# SH_SW2_V1_0.net
KiCad netlist of a schematic drawn in Altium Designer
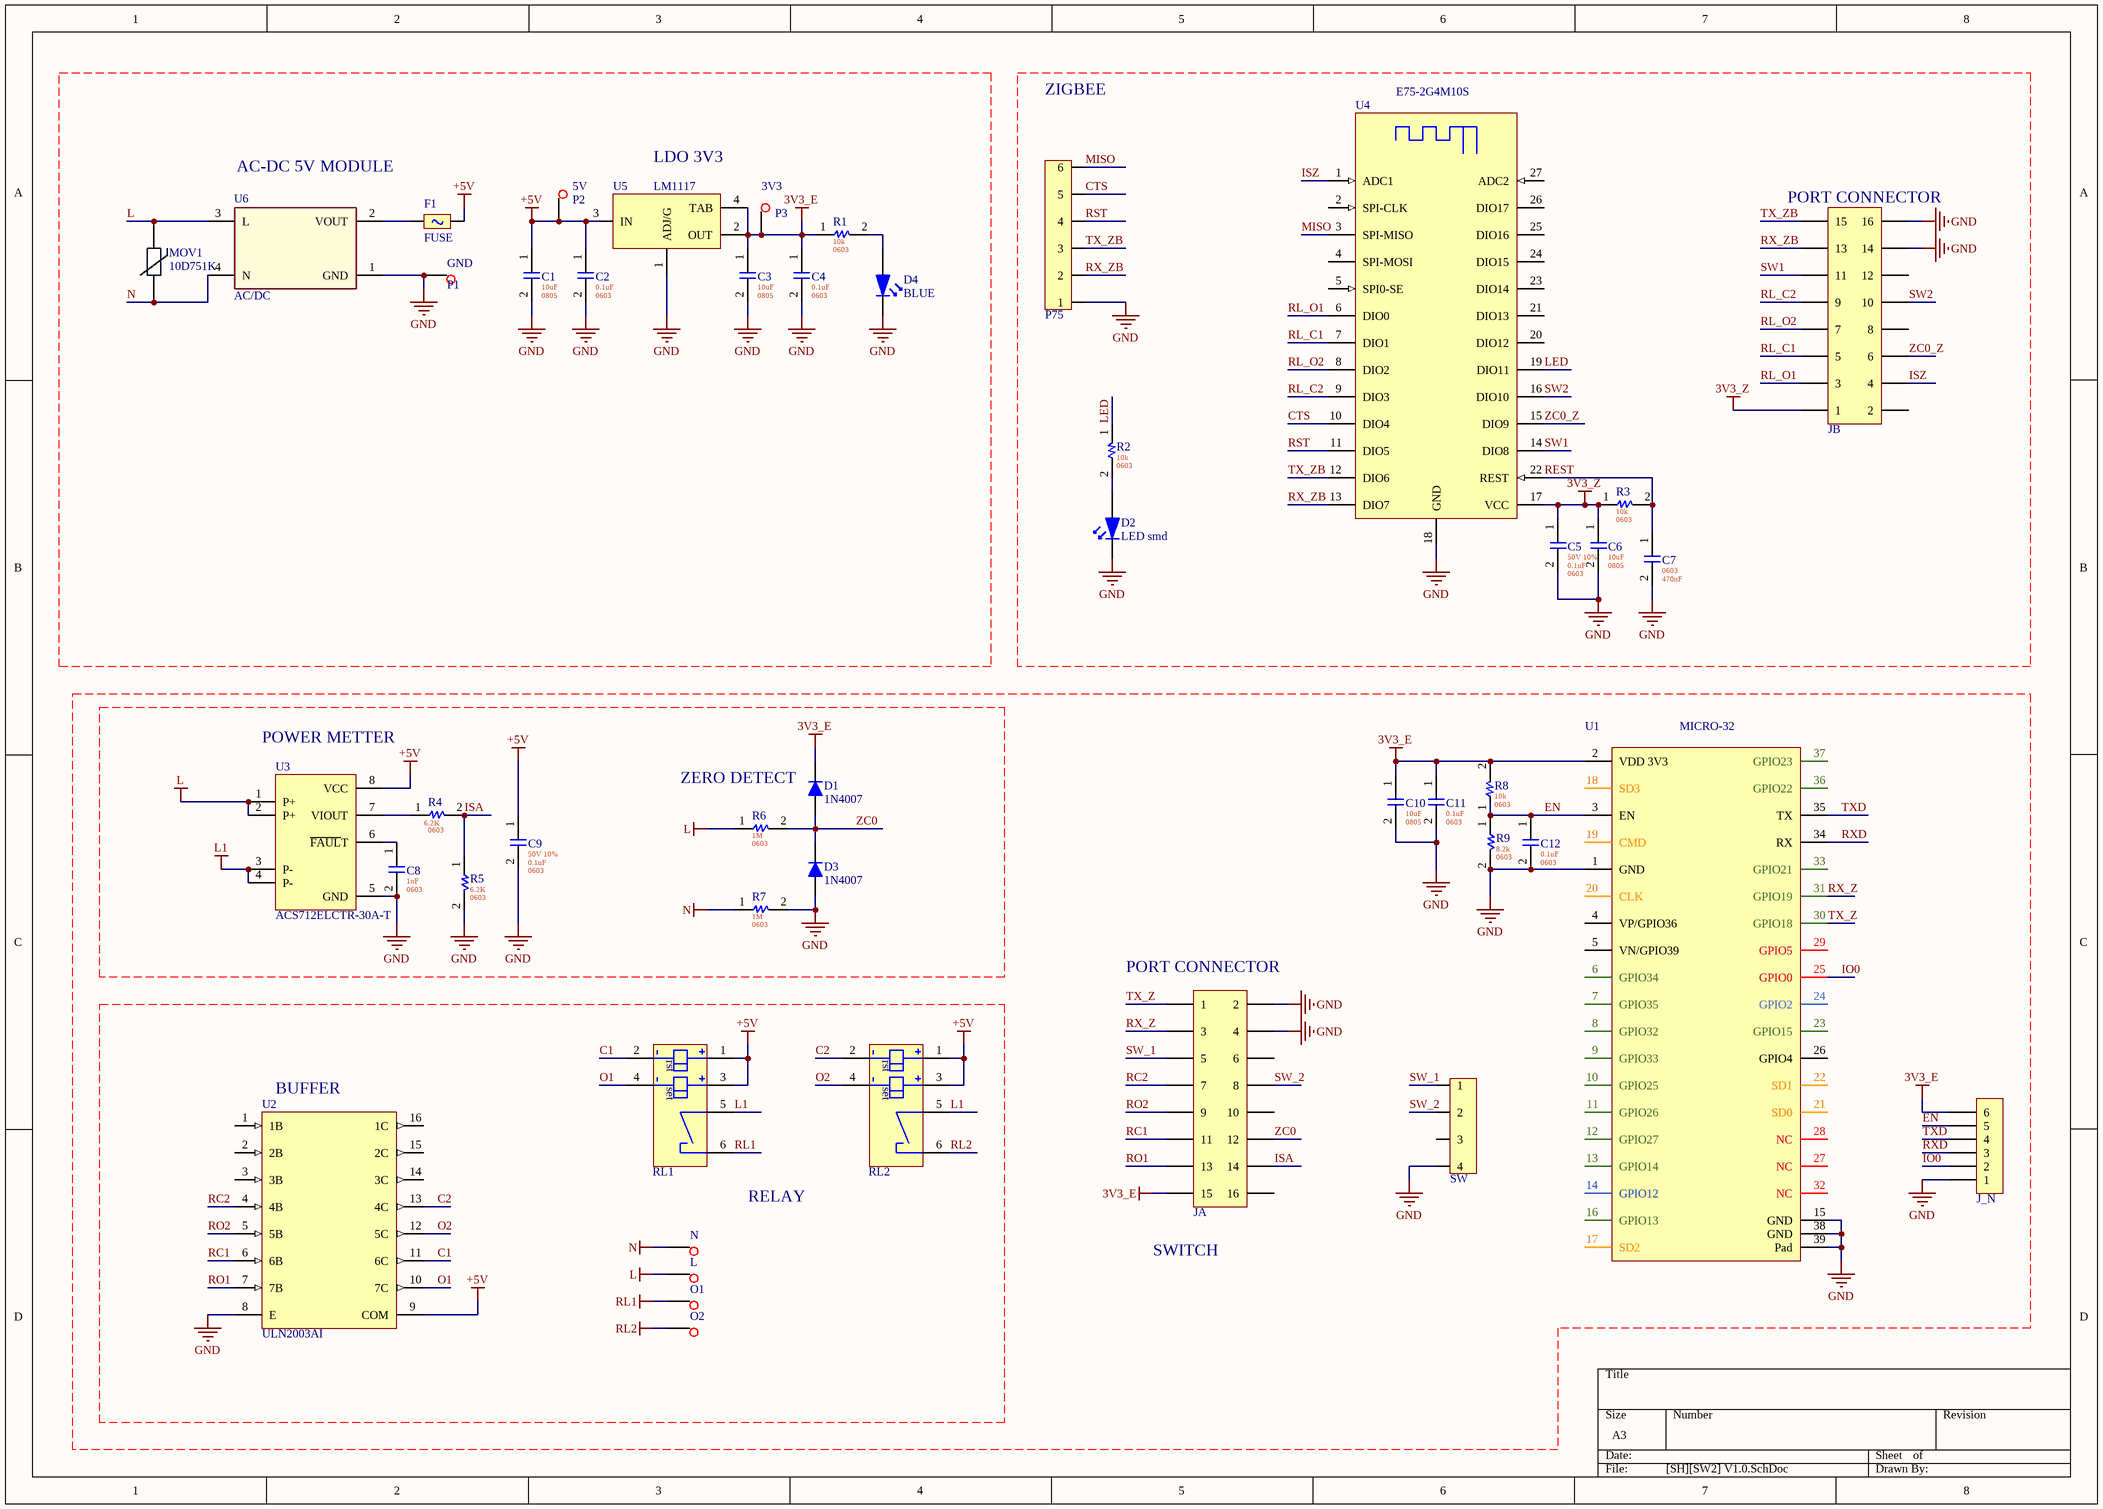
[diagram p0: [SH][SW2] V1.0.SchDoc]

(export (version "E")
  (design (tool "Eeschema 10.0.6"))
  (components
    (comp (ref "3V3") (value "P3") (footprint "TEXT_POINT") (libsource (lib "Kienlib") (part "P1")))
    (comp (ref "5V") (value "P2") (footprint "TEXT_POINT") (libsource (lib "Kienlib") (part "P1")))
    (comp (ref "C1")
      (value "10uF")
      (footprint "0805 C")
      (description "CAP CER 10uF 50V 10% 0805 SMD")
      (fields (field (name "FP") "0805") (field (name "CREATOR") "MMUOP"))
      (libsource (lib "Capacitor") (part "0805 10uF CER"))
    )
    (comp (ref "C2")
      (value "0.1uF")
      (footprint "0603 C")
      (description "CAP CER 0.1uF 50V 10% 0603 SMD")
      (fields (field (name "FP") "0603") (field (name "CREATOR") "MMUOP"))
      (libsource (lib "Capacitor") (part "0603 0.1uF CER"))
    )
    (comp (ref "C3")
      (value "10uF")
      (footprint "0805 C")
      (description "CAP CER 10uF 50V 10% 0805 SMD")
      (fields (field (name "FP") "0805") (field (name "CREATOR") "MMUOP"))
      (libsource (lib "Capacitor") (part "0805 10uF CER"))
    )
    (comp (ref "C4")
      (value "0.1uF")
      (footprint "0603 C")
      (description "CAP CER 0.1uF 50V 10% 0603 SMD")
      (fields (field (name "FP") "0603") (field (name "CREATOR") "MMUOP"))
      (libsource (lib "Capacitor") (part "0603 0.1uF CER"))
    )
    (comp (ref "C5")
      (value "0.1uF")
      (footprint "0603 C")
      (description "CAP CER 0.1uF 50V 10% 0603 SMD")
      (fields
        (field (name "VOLTAGE + TOLE") "50V 10%")
        (field (name "FP") "0603")
        (field (name "CREATOR") "MMUOP")
      )
      (libsource (lib "Capacitor") (part "0603 0.1uF CER"))
    )
    (comp (ref "C6")
      (value "10uF")
      (footprint "0805 C")
      (description "CAP CER 10uF 50V 10% 0805 SMD")
      (fields (field (name "FP") "0805") (field (name "CREATOR") "MMUOP"))
      (libsource (lib "Capacitor") (part "0805 10uF CER"))
    )
    (comp (ref "C7")
      (value "470nF")
      (footprint "0603 C")
      (description "CAP CER 470nF 50V 10% 0603 SMD")
      (fields (field (name "FP") "0603") (field (name "CREATOR") "MMUOP"))
      (libsource (lib "Capacitor") (part "0603 470nF CER"))
    )
    (comp (ref "C8")
      (value "1nF")
      (footprint "0603 C")
      (description "CAP CER 1nF 50V 10% 0603 SMD")
      (fields (field (name "FP") "0603") (field (name "CREATOR") "MMUOP"))
      (libsource (lib "Capacitor") (part "0603 1nF CER"))
    )
    (comp (ref "C9")
      (value "0.1uF")
      (footprint "0603 C")
      (description "CAP CER 0.1uF 50V 10% 0603 SMD")
      (fields
        (field (name "VOLTAGE + TOLE") "50V 10%")
        (field (name "FP") "0603")
        (field (name "CREATOR") "MMUOP")
      )
      (libsource (lib "Capacitor") (part "0603 0.1uF CER"))
    )
    (comp (ref "C10")
      (value "10uF")
      (footprint "0805 C")
      (description "CAP CER 10uF 50V 10% 0805 SMD")
      (fields (field (name "FP") "0805") (field (name "CREATOR") "MMUOP"))
      (libsource (lib "Capacitor") (part "0805 10uF CER"))
    )
    (comp (ref "C11")
      (value "0.1uF")
      (footprint "0603 C")
      (description "CAP CER 0.1uF 50V 10% 0603 SMD")
      (fields (field (name "FP") "0603") (field (name "CREATOR") "MMUOP"))
      (libsource (lib "Capacitor") (part "0603 0.1uF CER"))
    )
    (comp (ref "C12")
      (value "0.1uF")
      (footprint "0603 C")
      (description "CAP CER 0.1uF 50V 10% 0603 SMD")
      (fields (field (name "FP") "0603") (field (name "CREATOR") "MMUOP"))
      (libsource (lib "Capacitor") (part "0603 0.1uF CER"))
    )
    (comp (ref "D1")
      (value "1N4007")
      (footprint "SOD-123")
      (libsource (lib "Kienlib") (part "Diode schottky"))
    )
    (comp (ref "D2") (value "LED smd") (footprint "Led 1206") (libsource (lib "Kienlib") (part "LED smd")))
    (comp (ref "D3")
      (value "1N4007")
      (footprint "SOD-123")
      (libsource (lib "Kienlib") (part "Diode schottky"))
    )
    (comp (ref "D4") (value "BLUE") (footprint "Led 1206") (libsource (lib "Kienlib") (part "LED smd")))
    (comp (ref "F1") (value "FUSE") (footprint "1812") (libsource (lib "Kienlib") (part "FUSE")))
    (comp (ref "GND") (value "P1") (footprint "TEXT_POINT") (libsource (lib "Kienlib") (part "P1")))
    (comp (ref "JA")
      (value "rao doi")
      (footprint "P2X8 - 2.0mm - female - SMD")
      (libsource (lib "") (part "P2x8_1"))
    )
    (comp (ref "JB")
      (value "rao doi")
      (footprint "P2X8 - 2.0mm - SMD")
      (libsource (lib "Kienlib") (part "P2x8"))
    )
    (comp (ref "J_N") (value "P6") (footprint "P6 - 1.27MM") (libsource (lib "") (part "P6_1")))
    (comp (ref "L") (value "P1") (footprint "P1 - BRASS TERMINAL") (libsource (lib "Kienlib") (part "P1")))
    (comp (ref "MOV1")
      (value "10D751K")
      (footprint "MOV")
      (description "750V")
      (libsource (lib "Kienlib") (part "VARISTOR"))
    )
    (comp (ref "N") (value "P1") (footprint "P1 - BRASS TERMINAL") (libsource (lib "Kienlib") (part "P1")))
    (comp (ref "O1") (value "P1") (footprint "P1 - BRASS TERMINAL") (libsource (lib "Kienlib") (part "P1")))
    (comp (ref "O2") (value "P1") (footprint "P1 - BRASS TERMINAL") (libsource (lib "Kienlib") (part "P1")))
    (comp (ref "P75") (value "P6") (footprint "P6 - 1.27MM") (libsource (lib "Kienlib") (part "P6")))
    (comp (ref "R1")
      (value "10k")
      (footprint "0603 R")
      (description "10k 1% 0603 SMD")
      (fields (field (name "FP") "0603") (field (name "CREATOR") "MMUOP"))
      (libsource (lib "Res") (part "0603 10k 1%"))
    )
    (comp (ref "R2")
      (value "10k")
      (footprint "0603 R")
      (description "10k 1% 0603 SMD")
      (fields (field (name "FP") "0603") (field (name "CREATOR") "MMUOP"))
      (libsource (lib "Res") (part "0603 10k 1%"))
    )
    (comp (ref "R3")
      (value "10k")
      (footprint "0603 R")
      (description "10k 1% 0603 SMD")
      (fields (field (name "FP") "0603") (field (name "CREATOR") "MMUOP"))
      (libsource (lib "Res") (part "0603 10k 1%"))
    )
    (comp (ref "R4")
      (value "6.2K")
      (footprint "0603 R")
      (description "8.2k 1% 0603 SMD")
      (fields (field (name "FP") "0603") (field (name "Comment") "8.2k") (field (name "CREATOR") "MMUOP"))
      (libsource (lib "Res") (part "0603 8.2k 1%"))
    )
    (comp (ref "R5")
      (value "6.2K")
      (footprint "0603 R")
      (description "8.2k 1% 0603 SMD")
      (fields (field (name "FP") "0603") (field (name "Comment") "8.2k") (field (name "CREATOR") "MMUOP"))
      (libsource (lib "Res") (part "0603 8.2k 1%"))
    )
    (comp (ref "R6")
      (value "1M")
      (footprint "0603 R")
      (description "1M 1% 0603 SMD")
      (fields (field (name "FP") "0603") (field (name "CREATOR") "MMUOP"))
      (libsource (lib "Res") (part "0603 1M 1%"))
    )
    (comp (ref "R7")
      (value "1M")
      (footprint "0603 R")
      (description "1M 1% 0603 SMD")
      (fields (field (name "FP") "0603") (field (name "CREATOR") "MMUOP"))
      (libsource (lib "Res") (part "0603 1M 1%"))
    )
    (comp (ref "R8")
      (value "10k")
      (footprint "0603 R")
      (description "10k 1% 0603 SMD")
      (fields (field (name "FP") "0603") (field (name "CREATOR") "MMUOP"))
      (libsource (lib "Res") (part "0603 10k 1%"))
    )
    (comp (ref "R9")
      (value "8.2k")
      (footprint "0603 R")
      (description "8.2k 1% 0603 SMD")
      (fields (field (name "FP") "0603") (field (name "CREATOR") "MMUOP"))
      (libsource (lib "Res") (part "0603 8.2k 1%"))
    )
    (comp (ref "RL1")
      (value "RELAY CHOT")
      (footprint "HFE60")
      (libsource (lib "Kienlib") (part "RELAY CHOT"))
    )
    (comp (ref "RL2")
      (value "RELAY CHOT")
      (footprint "HFE60")
      (libsource (lib "Kienlib") (part "RELAY CHOT"))
    )
    (comp (ref "SW") (value "P4") (footprint "P4 2.54 RA header") (libsource (lib "Kienlib") (part "P4")))
    (comp (ref "U1")
      (value "MICRO-32")
      (footprint "ESP MICRO 32")
      (libsource (lib "Kienlib") (part "ESP MICRO-32_FIX"))
    )
    (comp (ref "U2")
      (value "ULN2003AI")
      (footprint "SOIC 16")
      (description "TRANS 7NPN DARL 50V 0.5A 16SO")
      (libsource (lib "Kienlib") (part "ULN2003AI"))
    )
    (comp (ref "U3")
      (value "ACS712ELCTR-30A-T")
      (footprint "SOIC 8")
      (description "ACS712ELCTR-20A  SOIC 8")
      (libsource (lib "Kienlib") (part "ACS71240"))
    )
    (comp (ref "U4")
      (value "E75-2G4M10S")
      (footprint "ebyte - E75-2G4M10S")
      (libsource (lib "Kienlib") (part "ebyte - E75-2G4M10S"))
    )
    (comp (ref "U5") (value "LM1117") (footprint "SOT23-4") (libsource (lib "Kienlib") (part "LM1117")))
    (comp (ref "U6") (value "AC/DC") (footprint "AC-DC 5V K4H24") (libsource (lib "Kienlib") (part "AC/DC")))
  )
  (nets
    (net (code "1") (name "+5V") (class "Default")
      (node (ref "5V") (pin "1") (pinfunction "P_1") (pintype "passive"))
      (node (ref "C1") (pin "1") (pinfunction "1_1") (pintype "passive"))
      (node (ref "C2") (pin "1") (pinfunction "1_1") (pintype "passive"))
      (node (ref "C9") (pin "1") (pinfunction "1_1") (pintype "passive"))
      (node (ref "F1") (pin "2") (pinfunction "2_2") (pintype "passive"))
      (node (ref "RL1") (pin "1") (pinfunction "1_1") (pintype "passive"))
      (node (ref "RL1") (pin "3") (pinfunction "3_3") (pintype "passive"))
      (node (ref "RL2") (pin "1") (pinfunction "1_1") (pintype "passive"))
      (node (ref "RL2") (pin "3") (pinfunction "3_3") (pintype "passive"))
      (node (ref "U2") (pin "9") (pinfunction "COM_9") (pintype "passive"))
      (node (ref "U3") (pin "8") (pinfunction "VCC_8") (pintype "passive"))
      (node (ref "U5") (pin "3") (pinfunction "IN_3") (pintype "passive"))
    )
    (net (code "2") (name "/C1") (class "Default")
      (node (ref "RL1") (pin "2") (pinfunction "2_2") (pintype "passive"))
      (node (ref "U2") (pin "11") (pinfunction "6C_11") (pintype "output"))
    )
    (net (code "3") (name "/C2") (class "Default")
      (node (ref "RL2") (pin "2") (pinfunction "2_2") (pintype "passive"))
      (node (ref "U2") (pin "13") (pinfunction "4C_13") (pintype "output"))
    )
    (net (code "4") (name "/CTS") (class "Default")
      (node (ref "P75") (pin "5") (pinfunction "5_5") (pintype "passive"))
      (node (ref "U4") (pin "10") (pinfunction "DIO4_10") (pintype "passive"))
    )
    (net (code "5") (name "/EN") (class "Default")
      (node (ref "C12") (pin "1") (pinfunction "1_1") (pintype "passive"))
      (node (ref "J_N") (pin "5") (pinfunction "5_5") (pintype "passive"))
      (node (ref "R8") (pin "1") (pinfunction "1_1") (pintype "passive"))
      (node (ref "R9") (pin "1") (pinfunction "1_1") (pintype "passive"))
      (node (ref "U1") (pin "3") (pinfunction "EN_3") (pintype "passive"))
    )
    (net (code "6") (name "/IO0") (class "Default")
      (node (ref "J_N") (pin "2") (pinfunction "2_2") (pintype "passive"))
      (node (ref "U1") (pin "25") (pinfunction "GPIO0_25") (pintype "passive"))
    )
    (net (code "7") (name "/ISA") (class "Default")
      (node (ref "JA") (pin "14") (pinfunction "14_14") (pintype "passive"))
      (node (ref "R4") (pin "2") (pinfunction "2_2") (pintype "passive"))
      (node (ref "R5") (pin "1") (pinfunction "1_1") (pintype "passive"))
    )
    (net (code "8") (name "/ISZ") (class "Default")
      (node (ref "JB") (pin "4") (pinfunction "4_4") (pintype "passive"))
      (node (ref "U4") (pin "1") (pinfunction "ADC1_1") (pintype "input"))
    )
    (net (code "9") (name "/LED") (class "Default")
      (node (ref "R2") (pin "1") (pinfunction "1_1") (pintype "passive"))
      (node (ref "U4") (pin "19") (pinfunction "DIO11_19") (pintype "passive"))
    )
    (net (code "10") (name "/MISO") (class "Default")
      (node (ref "P75") (pin "6") (pinfunction "6_6") (pintype "passive"))
      (node (ref "U4") (pin "3") (pinfunction "SPI-MISO_3") (pintype "passive"))
    )
    (net (code "11") (name "/O1") (class "Default")
      (node (ref "RL1") (pin "4") (pinfunction "4_4") (pintype "passive"))
      (node (ref "U2") (pin "10") (pinfunction "7C_10") (pintype "output"))
    )
    (net (code "12") (name "/O2") (class "Default")
      (node (ref "RL2") (pin "4") (pinfunction "4_4") (pintype "passive"))
      (node (ref "U2") (pin "12") (pinfunction "5C_12") (pintype "output"))
    )
    (net (code "13") (name "/RC1") (class "Default")
      (node (ref "JA") (pin "11") (pinfunction "11_11") (pintype "passive"))
      (node (ref "U2") (pin "6") (pinfunction "6B_6") (pintype "input"))
    )
    (net (code "14") (name "/RC2") (class "Default")
      (node (ref "JA") (pin "7") (pinfunction "7_7") (pintype "passive"))
      (node (ref "U2") (pin "4") (pinfunction "4B_4") (pintype "input"))
    )
    (net (code "15") (name "/REST") (class "Default")
      (node (ref "C7") (pin "1") (pinfunction "1_1") (pintype "passive"))
      (node (ref "R3") (pin "2") (pinfunction "2_2") (pintype "passive"))
      (node (ref "U4") (pin "22") (pinfunction "REST_22") (pintype "input"))
    )
    (net (code "16") (name "/RL_C1") (class "Default")
      (node (ref "JB") (pin "5") (pinfunction "5_5") (pintype "passive"))
      (node (ref "U4") (pin "7") (pinfunction "DIO1_7") (pintype "passive"))
    )
    (net (code "17") (name "/RL_C2") (class "Default")
      (node (ref "JB") (pin "9") (pinfunction "9_9") (pintype "passive"))
      (node (ref "U4") (pin "9") (pinfunction "DIO3_9") (pintype "passive"))
    )
    (net (code "18") (name "/RL_O1") (class "Default")
      (node (ref "JB") (pin "3") (pinfunction "3_3") (pintype "passive"))
      (node (ref "U4") (pin "6") (pinfunction "DIO0_6") (pintype "passive"))
    )
    (net (code "19") (name "/RL_O2") (class "Default")
      (node (ref "JB") (pin "7") (pinfunction "7_7") (pintype "passive"))
      (node (ref "U4") (pin "8") (pinfunction "DIO2_8") (pintype "passive"))
    )
    (net (code "20") (name "/RO1") (class "Default")
      (node (ref "JA") (pin "13") (pinfunction "13_13") (pintype "passive"))
      (node (ref "U2") (pin "7") (pinfunction "7B_7") (pintype "input"))
    )
    (net (code "21") (name "/RO2") (class "Default")
      (node (ref "JA") (pin "9") (pinfunction "9_9") (pintype "passive"))
      (node (ref "U2") (pin "5") (pinfunction "5B_5") (pintype "input"))
    )
    (net (code "22") (name "/RST") (class "Default")
      (node (ref "P75") (pin "4") (pinfunction "4_4") (pintype "passive"))
      (node (ref "U4") (pin "11") (pinfunction "DIO5_11") (pintype "passive"))
    )
    (net (code "23") (name "/RXD") (class "Default")
      (node (ref "J_N") (pin "3") (pinfunction "3_3") (pintype "passive"))
      (node (ref "U1") (pin "34") (pinfunction "RX_34") (pintype "passive"))
    )
    (net (code "24") (name "/RX_Z") (class "Default")
      (node (ref "JA") (pin "3") (pinfunction "3_3") (pintype "passive"))
      (node (ref "U1") (pin "31") (pinfunction "GPIO19_31") (pintype "passive"))
    )
    (net (code "25") (name "/RX_ZB") (class "Default")
      (node (ref "JB") (pin "13") (pinfunction "13_13") (pintype "passive"))
      (node (ref "P75") (pin "2") (pinfunction "2_2") (pintype "passive"))
      (node (ref "U4") (pin "13") (pinfunction "DIO7_13") (pintype "passive"))
    )
    (net (code "26") (name "/SW1") (class "Default")
      (node (ref "JB") (pin "11") (pinfunction "11_11") (pintype "passive"))
      (node (ref "U4") (pin "14") (pinfunction "DIO8_14") (pintype "passive"))
    )
    (net (code "27") (name "/SW2") (class "Default")
      (node (ref "JB") (pin "10") (pinfunction "10_10") (pintype "passive"))
      (node (ref "U4") (pin "16") (pinfunction "DIO10_16") (pintype "passive"))
    )
    (net (code "28") (name "/SW_1") (class "Default")
      (node (ref "JA") (pin "5") (pinfunction "5_5") (pintype "passive"))
      (node (ref "SW") (pin "1") (pinfunction "1_1") (pintype "passive"))
    )
    (net (code "29") (name "/SW_2") (class "Default")
      (node (ref "JA") (pin "8") (pinfunction "8_8") (pintype "passive"))
      (node (ref "SW") (pin "2") (pinfunction "2_2") (pintype "passive"))
    )
    (net (code "30") (name "/TXD") (class "Default")
      (node (ref "J_N") (pin "4") (pinfunction "4_4") (pintype "passive"))
      (node (ref "U1") (pin "35") (pinfunction "TX_35") (pintype "passive"))
    )
    (net (code "31") (name "/TX_Z") (class "Default")
      (node (ref "JA") (pin "1") (pinfunction "1_1") (pintype "passive"))
      (node (ref "U1") (pin "30") (pinfunction "GPIO18_30") (pintype "passive"))
    )
    (net (code "32") (name "/TX_ZB") (class "Default")
      (node (ref "JB") (pin "15") (pinfunction "15_15") (pintype "passive"))
      (node (ref "P75") (pin "3") (pinfunction "3_3") (pintype "passive"))
      (node (ref "U4") (pin "12") (pinfunction "DIO6_12") (pintype "passive"))
    )
    (net (code "33") (name "/ZC0") (class "Default")
      (node (ref "D1") (pin "1") (pinfunction "1_1") (pintype "passive"))
      (node (ref "D3") (pin "2") (pinfunction "2_2") (pintype "passive"))
      (node (ref "JA") (pin "12") (pinfunction "12_12") (pintype "passive"))
      (node (ref "R6") (pin "2") (pinfunction "2_2") (pintype "passive"))
    )
    (net (code "34") (name "/ZC0_Z") (class "Default")
      (node (ref "JB") (pin "6") (pinfunction "6_6") (pintype "passive"))
      (node (ref "U4") (pin "15") (pinfunction "DIO9_15") (pintype "passive"))
    )
    (net (code "35") (name "3V3_E") (class "Default")
      (node (ref "3V3") (pin "1") (pinfunction "P_1") (pintype "passive"))
      (node (ref "C10") (pin "1") (pinfunction "1_1") (pintype "passive"))
      (node (ref "C11") (pin "1") (pinfunction "1_1") (pintype "passive"))
      (node (ref "C3") (pin "1") (pinfunction "1_1") (pintype "passive"))
      (node (ref "C4") (pin "1") (pinfunction "1_1") (pintype "passive"))
      (node (ref "D1") (pin "2") (pinfunction "2_2") (pintype "passive"))
      (node (ref "JA") (pin "15") (pinfunction "15_15") (pintype "passive"))
      (node (ref "J_N") (pin "6") (pinfunction "6_6") (pintype "passive"))
      (node (ref "R1") (pin "1") (pinfunction "1_1") (pintype "passive"))
      (node (ref "R8") (pin "2") (pinfunction "2_2") (pintype "passive"))
      (node (ref "U1") (pin "2") (pinfunction "VDD_3V3_2") (pintype "passive"))
      (node (ref "U5") (pin "2") (pinfunction "OUT_2") (pintype "passive"))
      (node (ref "U5") (pin "4") (pinfunction "TAB_4") (pintype "passive"))
    )
    (net (code "36") (name "3V3_Z") (class "Default")
      (node (ref "C5") (pin "1") (pinfunction "1_1") (pintype "passive"))
      (node (ref "C6") (pin "1") (pinfunction "1_1") (pintype "passive"))
      (node (ref "JB") (pin "1") (pinfunction "1_1") (pintype "passive"))
      (node (ref "R3") (pin "1") (pinfunction "1_1") (pintype "passive"))
      (node (ref "U4") (pin "17") (pinfunction "VCC_17") (pintype "passive"))
    )
    (net (code "37") (name "GND") (class "Default")
      (node (ref "C1") (pin "2") (pinfunction "2_2") (pintype "passive"))
      (node (ref "C10") (pin "2") (pinfunction "2_2") (pintype "passive"))
      (node (ref "C11") (pin "2") (pinfunction "2_2") (pintype "passive"))
      (node (ref "C12") (pin "2") (pinfunction "2_2") (pintype "passive"))
      (node (ref "C2") (pin "2") (pinfunction "2_2") (pintype "passive"))
      (node (ref "C3") (pin "2") (pinfunction "2_2") (pintype "passive"))
      (node (ref "C4") (pin "2") (pinfunction "2_2") (pintype "passive"))
      (node (ref "C5") (pin "2") (pinfunction "2_2") (pintype "passive"))
      (node (ref "C6") (pin "2") (pinfunction "2_2") (pintype "passive"))
      (node (ref "C7") (pin "2") (pinfunction "2_2") (pintype "passive"))
      (node (ref "C8") (pin "2") (pinfunction "2_2") (pintype "passive"))
      (node (ref "C9") (pin "2") (pinfunction "2_2") (pintype "passive"))
      (node (ref "D2") (pin "2") (pinfunction "2_2") (pintype "passive"))
      (node (ref "D3") (pin "1") (pinfunction "1_1") (pintype "passive"))
      (node (ref "D4") (pin "2") (pinfunction "2_2") (pintype "passive"))
      (node (ref "GND") (pin "1") (pinfunction "P_1") (pintype "passive"))
      (node (ref "JA") (pin "2") (pinfunction "2_2") (pintype "passive"))
      (node (ref "JA") (pin "4") (pinfunction "4_4") (pintype "passive"))
      (node (ref "JB") (pin "14") (pinfunction "14_14") (pintype "passive"))
      (node (ref "JB") (pin "16") (pinfunction "16_16") (pintype "passive"))
      (node (ref "J_N") (pin "1") (pinfunction "1_1") (pintype "passive"))
      (node (ref "P75") (pin "1") (pinfunction "1_1") (pintype "passive"))
      (node (ref "R5") (pin "2") (pinfunction "2_2") (pintype "passive"))
      (node (ref "R7") (pin "2") (pinfunction "2_2") (pintype "passive"))
      (node (ref "R9") (pin "2") (pinfunction "2_2") (pintype "passive"))
      (node (ref "SW") (pin "4") (pinfunction "4_4") (pintype "passive"))
      (node (ref "U1") (pin "1") (pinfunction "GND_1") (pintype "passive"))
      (node (ref "U1") (pin "15") (pinfunction "GND_15") (pintype "passive"))
      (node (ref "U1") (pin "38") (pinfunction "GND_38") (pintype "passive"))
      (node (ref "U1") (pin "39") (pinfunction "Pad_39") (pintype "passive"))
      (node (ref "U2") (pin "8") (pinfunction "E_8") (pintype "passive"))
      (node (ref "U3") (pin "5") (pinfunction "GND_5") (pintype "passive"))
      (node (ref "U4") (pin "18") (pinfunction "GND_18") (pintype "passive"))
      (node (ref "U5") (pin "1") (pinfunction "ADJ/G_1") (pintype "passive"))
      (node (ref "U6") (pin "1") (pinfunction "GND_1") (pintype "passive"))
    )
    (net (code "38") (name "L") (class "Default")
      (node (ref "L") (pin "1") (pinfunction "P_1") (pintype "passive"))
      (node (ref "MOV1") (pin "2") (pinfunction "2_2") (pintype "passive"))
      (node (ref "R6") (pin "1") (pinfunction "1_1") (pintype "passive"))
      (node (ref "U3") (pin "1") (pinfunction "P+_1") (pintype "passive"))
      (node (ref "U3") (pin "2") (pinfunction "P+_2") (pintype "passive"))
      (node (ref "U6") (pin "3") (pinfunction "L_3") (pintype "passive"))
    )
    (net (code "39") (name "L1") (class "Default")
      (node (ref "RL1") (pin "5") (pinfunction "5_5") (pintype "passive"))
      (node (ref "RL2") (pin "5") (pinfunction "5_5") (pintype "passive"))
      (node (ref "U3") (pin "3") (pinfunction "P-_3") (pintype "passive"))
      (node (ref "U3") (pin "4") (pinfunction "P-_4") (pintype "passive"))
    )
    (net (code "40") (name "N") (class "Default")
      (node (ref "MOV1") (pin "1") (pinfunction "1_1") (pintype "passive"))
      (node (ref "N") (pin "1") (pinfunction "P_1") (pintype "passive"))
      (node (ref "R7") (pin "1") (pinfunction "1_1") (pintype "passive"))
      (node (ref "U6") (pin "4") (pinfunction "N_4") (pintype "passive"))
    )
    (net (code "41") (name "Net-(D2-Pad1)") (class "Default")
      (node (ref "D2") (pin "1") (pinfunction "1_1") (pintype "passive"))
      (node (ref "R2") (pin "2") (pinfunction "2_2") (pintype "passive"))
    )
    (net (code "42") (name "Net-(D4-Pad1)") (class "Default")
      (node (ref "D4") (pin "1") (pinfunction "1_1") (pintype "passive"))
      (node (ref "R1") (pin "2") (pinfunction "2_2") (pintype "passive"))
    )
    (net (code "43") (name "Net-(U3-VIOUT)") (class "Default")
      (node (ref "R4") (pin "1") (pinfunction "1_1") (pintype "passive"))
      (node (ref "U3") (pin "7") (pinfunction "VIOUT_7") (pintype "passive"))
    )
    (net (code "44") (name "Net-(U3-~{FAUL}T)") (class "Default")
      (node (ref "C8") (pin "1") (pinfunction "1_1") (pintype "passive"))
      (node (ref "U3") (pin "6") (pinfunction "~{FAUL}T_6") (pintype "passive"))
    )
    (net (code "45") (name "Net-(U6-VOUT)") (class "Default")
      (node (ref "F1") (pin "1") (pinfunction "1_1") (pintype "passive"))
      (node (ref "U6") (pin "2") (pinfunction "VOUT_2") (pintype "passive"))
    )
    (net (code "46") (name "RL1") (class "Default")
      (node (ref "O1") (pin "1") (pinfunction "P_1") (pintype "passive"))
      (node (ref "RL1") (pin "6") (pinfunction "6_6") (pintype "passive"))
    )
    (net (code "47") (name "RL2") (class "Default")
      (node (ref "O2") (pin "1") (pinfunction "P_1") (pintype "passive"))
      (node (ref "RL2") (pin "6") (pinfunction "6_6") (pintype "passive"))
    )
    (net (code "48") (name "unconnected-(JA-Pad6)") (class "Default")
      (node (ref "JA") (pin "6") (pinfunction "6_6") (pintype "passive"))
    )
    (net (code "49") (name "unconnected-(JA-Pad10)") (class "Default")
      (node (ref "JA") (pin "10") (pinfunction "10_10") (pintype "passive"))
    )
    (net (code "50") (name "unconnected-(JA-Pad16)") (class "Default")
      (node (ref "JA") (pin "16") (pinfunction "16_16") (pintype "passive"))
    )
    (net (code "51") (name "unconnected-(JB-Pad2)") (class "Default")
      (node (ref "JB") (pin "2") (pinfunction "2_2") (pintype "passive"))
    )
    (net (code "52") (name "unconnected-(JB-Pad8)") (class "Default")
      (node (ref "JB") (pin "8") (pinfunction "8_8") (pintype "passive"))
    )
    (net (code "53") (name "unconnected-(JB-Pad12)") (class "Default")
      (node (ref "JB") (pin "12") (pinfunction "12_12") (pintype "passive"))
    )
    (net (code "54") (name "unconnected-(SW-Pad3)") (class "Default")
      (node (ref "SW") (pin "3") (pinfunction "3_3") (pintype "passive"))
    )
    (net (code "55") (name "unconnected-(U1-CLK-Pad20)") (class "Default")
      (node (ref "U1") (pin "20") (pinfunction "CLK_20") (pintype "passive"))
    )
    (net (code "56") (name "unconnected-(U1-CMD-Pad19)") (class "Default")
      (node (ref "U1") (pin "19") (pinfunction "CMD_19") (pintype "passive"))
    )
    (net (code "57") (name "unconnected-(U1-GPIO2-Pad24)") (class "Default")
      (node (ref "U1") (pin "24") (pinfunction "GPIO2_24") (pintype "passive"))
    )
    (net (code "58") (name "unconnected-(U1-GPIO4-Pad26)") (class "Default")
      (node (ref "U1") (pin "26") (pinfunction "GPIO4_26") (pintype "passive"))
    )
    (net (code "59") (name "unconnected-(U1-GPIO5-Pad29)") (class "Default")
      (node (ref "U1") (pin "29") (pinfunction "GPIO5_29") (pintype "passive"))
    )
    (net (code "60") (name "unconnected-(U1-GPIO12-Pad14)") (class "Default")
      (node (ref "U1") (pin "14") (pinfunction "GPIO12_14") (pintype "passive"))
    )
    (net (code "61") (name "unconnected-(U1-GPIO13-Pad16)") (class "Default")
      (node (ref "U1") (pin "16") (pinfunction "GPIO13_16") (pintype "passive"))
    )
    (net (code "62") (name "unconnected-(U1-GPIO14-Pad13)") (class "Default")
      (node (ref "U1") (pin "13") (pinfunction "GPIO14_13") (pintype "passive"))
    )
    (net (code "63") (name "unconnected-(U1-GPIO15-Pad23)") (class "Default")
      (node (ref "U1") (pin "23") (pinfunction "GPIO15_23") (pintype "passive"))
    )
    (net (code "64") (name "unconnected-(U1-GPIO21-Pad33)") (class "Default")
      (node (ref "U1") (pin "33") (pinfunction "GPIO21_33") (pintype "passive"))
    )
    (net (code "65") (name "unconnected-(U1-GPIO22-Pad36)") (class "Default")
      (node (ref "U1") (pin "36") (pinfunction "GPIO22_36") (pintype "passive"))
    )
    (net (code "66") (name "unconnected-(U1-GPIO23-Pad37)") (class "Default")
      (node (ref "U1") (pin "37") (pinfunction "GPIO23_37") (pintype "passive"))
    )
    (net (code "67") (name "unconnected-(U1-GPIO25-Pad10)") (class "Default")
      (node (ref "U1") (pin "10") (pinfunction "GPIO25_10") (pintype "passive"))
    )
    (net (code "68") (name "unconnected-(U1-GPIO26-Pad11)") (class "Default")
      (node (ref "U1") (pin "11") (pinfunction "GPIO26_11") (pintype "passive"))
    )
    (net (code "69") (name "unconnected-(U1-GPIO27-Pad12)") (class "Default")
      (node (ref "U1") (pin "12") (pinfunction "GPIO27_12") (pintype "passive"))
    )
    (net (code "70") (name "unconnected-(U1-GPIO32-Pad8)") (class "Default")
      (node (ref "U1") (pin "8") (pinfunction "GPIO32_8") (pintype "passive"))
    )
    (net (code "71") (name "unconnected-(U1-GPIO33-Pad9)") (class "Default")
      (node (ref "U1") (pin "9") (pinfunction "GPIO33_9") (pintype "passive"))
    )
    (net (code "72") (name "unconnected-(U1-GPIO34-Pad6)") (class "Default")
      (node (ref "U1") (pin "6") (pinfunction "GPIO34_6") (pintype "passive"))
    )
    (net (code "73") (name "unconnected-(U1-GPIO35-Pad7)") (class "Default")
      (node (ref "U1") (pin "7") (pinfunction "GPIO35_7") (pintype "passive"))
    )
    (net (code "74") (name "unconnected-(U1-NC-Pad27)") (class "Default")
      (node (ref "U1") (pin "27") (pinfunction "NC_27") (pintype "passive"))
    )
    (net (code "75") (name "unconnected-(U1-NC-Pad28)") (class "Default")
      (node (ref "U1") (pin "28") (pinfunction "NC_28") (pintype "passive"))
    )
    (net (code "76") (name "unconnected-(U1-NC-Pad32)") (class "Default")
      (node (ref "U1") (pin "32") (pinfunction "NC_32") (pintype "passive"))
    )
    (net (code "77") (name "unconnected-(U1-SD0-Pad21)") (class "Default")
      (node (ref "U1") (pin "21") (pinfunction "SD0_21") (pintype "passive"))
    )
    (net (code "78") (name "unconnected-(U1-SD1-Pad22)") (class "Default")
      (node (ref "U1") (pin "22") (pinfunction "SD1_22") (pintype "passive"))
    )
    (net (code "79") (name "unconnected-(U1-SD2-Pad17)") (class "Default")
      (node (ref "U1") (pin "17") (pinfunction "SD2_17") (pintype "passive"))
    )
    (net (code "80") (name "unconnected-(U1-SD3-Pad18)") (class "Default")
      (node (ref "U1") (pin "18") (pinfunction "SD3_18") (pintype "passive"))
    )
    (net (code "81") (name "unconnected-(U1-VN{slash}GPIO39-Pad5)") (class "Default")
      (node (ref "U1") (pin "5") (pinfunction "VN/GPIO39_5") (pintype "passive"))
    )
    (net (code "82") (name "unconnected-(U1-VP{slash}GPIO36-Pad4)") (class "Default")
      (node (ref "U1") (pin "4") (pinfunction "VP/GPIO36_4") (pintype "passive"))
    )
    (net (code "83") (name "unconnected-(U2-1B-Pad1)") (class "Default")
      (node (ref "U2") (pin "1") (pinfunction "1B_1") (pintype "input"))
    )
    (net (code "84") (name "unconnected-(U2-1C-Pad16)") (class "Default")
      (node (ref "U2") (pin "16") (pinfunction "1C_16") (pintype "output"))
    )
    (net (code "85") (name "unconnected-(U2-2B-Pad2)") (class "Default")
      (node (ref "U2") (pin "2") (pinfunction "2B_2") (pintype "input"))
    )
    (net (code "86") (name "unconnected-(U2-2C-Pad15)") (class "Default")
      (node (ref "U2") (pin "15") (pinfunction "2C_15") (pintype "output"))
    )
    (net (code "87") (name "unconnected-(U2-3B-Pad3)") (class "Default")
      (node (ref "U2") (pin "3") (pinfunction "3B_3") (pintype "input"))
    )
    (net (code "88") (name "unconnected-(U2-3C-Pad14)") (class "Default")
      (node (ref "U2") (pin "14") (pinfunction "3C_14") (pintype "output"))
    )
    (net (code "89") (name "unconnected-(U4-ADC2-Pad27)") (class "Default")
      (node (ref "U4") (pin "27") (pinfunction "ADC2_27") (pintype "input"))
    )
    (net (code "90") (name "unconnected-(U4-DIO12-Pad20)") (class "Default")
      (node (ref "U4") (pin "20") (pinfunction "DIO12_20") (pintype "passive"))
    )
    (net (code "91") (name "unconnected-(U4-DIO13-Pad21)") (class "Default")
      (node (ref "U4") (pin "21") (pinfunction "DIO13_21") (pintype "passive"))
    )
    (net (code "92") (name "unconnected-(U4-DIO14-Pad23)") (class "Default")
      (node (ref "U4") (pin "23") (pinfunction "DIO14_23") (pintype "passive"))
    )
    (net (code "93") (name "unconnected-(U4-DIO15-Pad24)") (class "Default")
      (node (ref "U4") (pin "24") (pinfunction "DIO15_24") (pintype "passive"))
    )
    (net (code "94") (name "unconnected-(U4-DIO16-Pad25)") (class "Default")
      (node (ref "U4") (pin "25") (pinfunction "DIO16_25") (pintype "passive"))
    )
    (net (code "95") (name "unconnected-(U4-DIO17-Pad26)") (class "Default")
      (node (ref "U4") (pin "26") (pinfunction "DIO17_26") (pintype "passive"))
    )
    (net (code "96") (name "unconnected-(U4-SPI-CLK-Pad2)") (class "Default")
      (node (ref "U4") (pin "2") (pinfunction "SPI-CLK_2") (pintype "input"))
    )
    (net (code "97") (name "unconnected-(U4-SPI-MOSI-Pad4)") (class "Default")
      (node (ref "U4") (pin "4") (pinfunction "SPI-MOSI_4") (pintype "passive"))
    )
    (net (code "98") (name "unconnected-(U4-SPI0-SE-Pad5)") (class "Default")
      (node (ref "U4") (pin "5") (pinfunction "SPI0-SE_5") (pintype "input"))
    )
  )
)
